# LPDDR4.net
KiCad netlist of a schematic drawn in Altium Designer
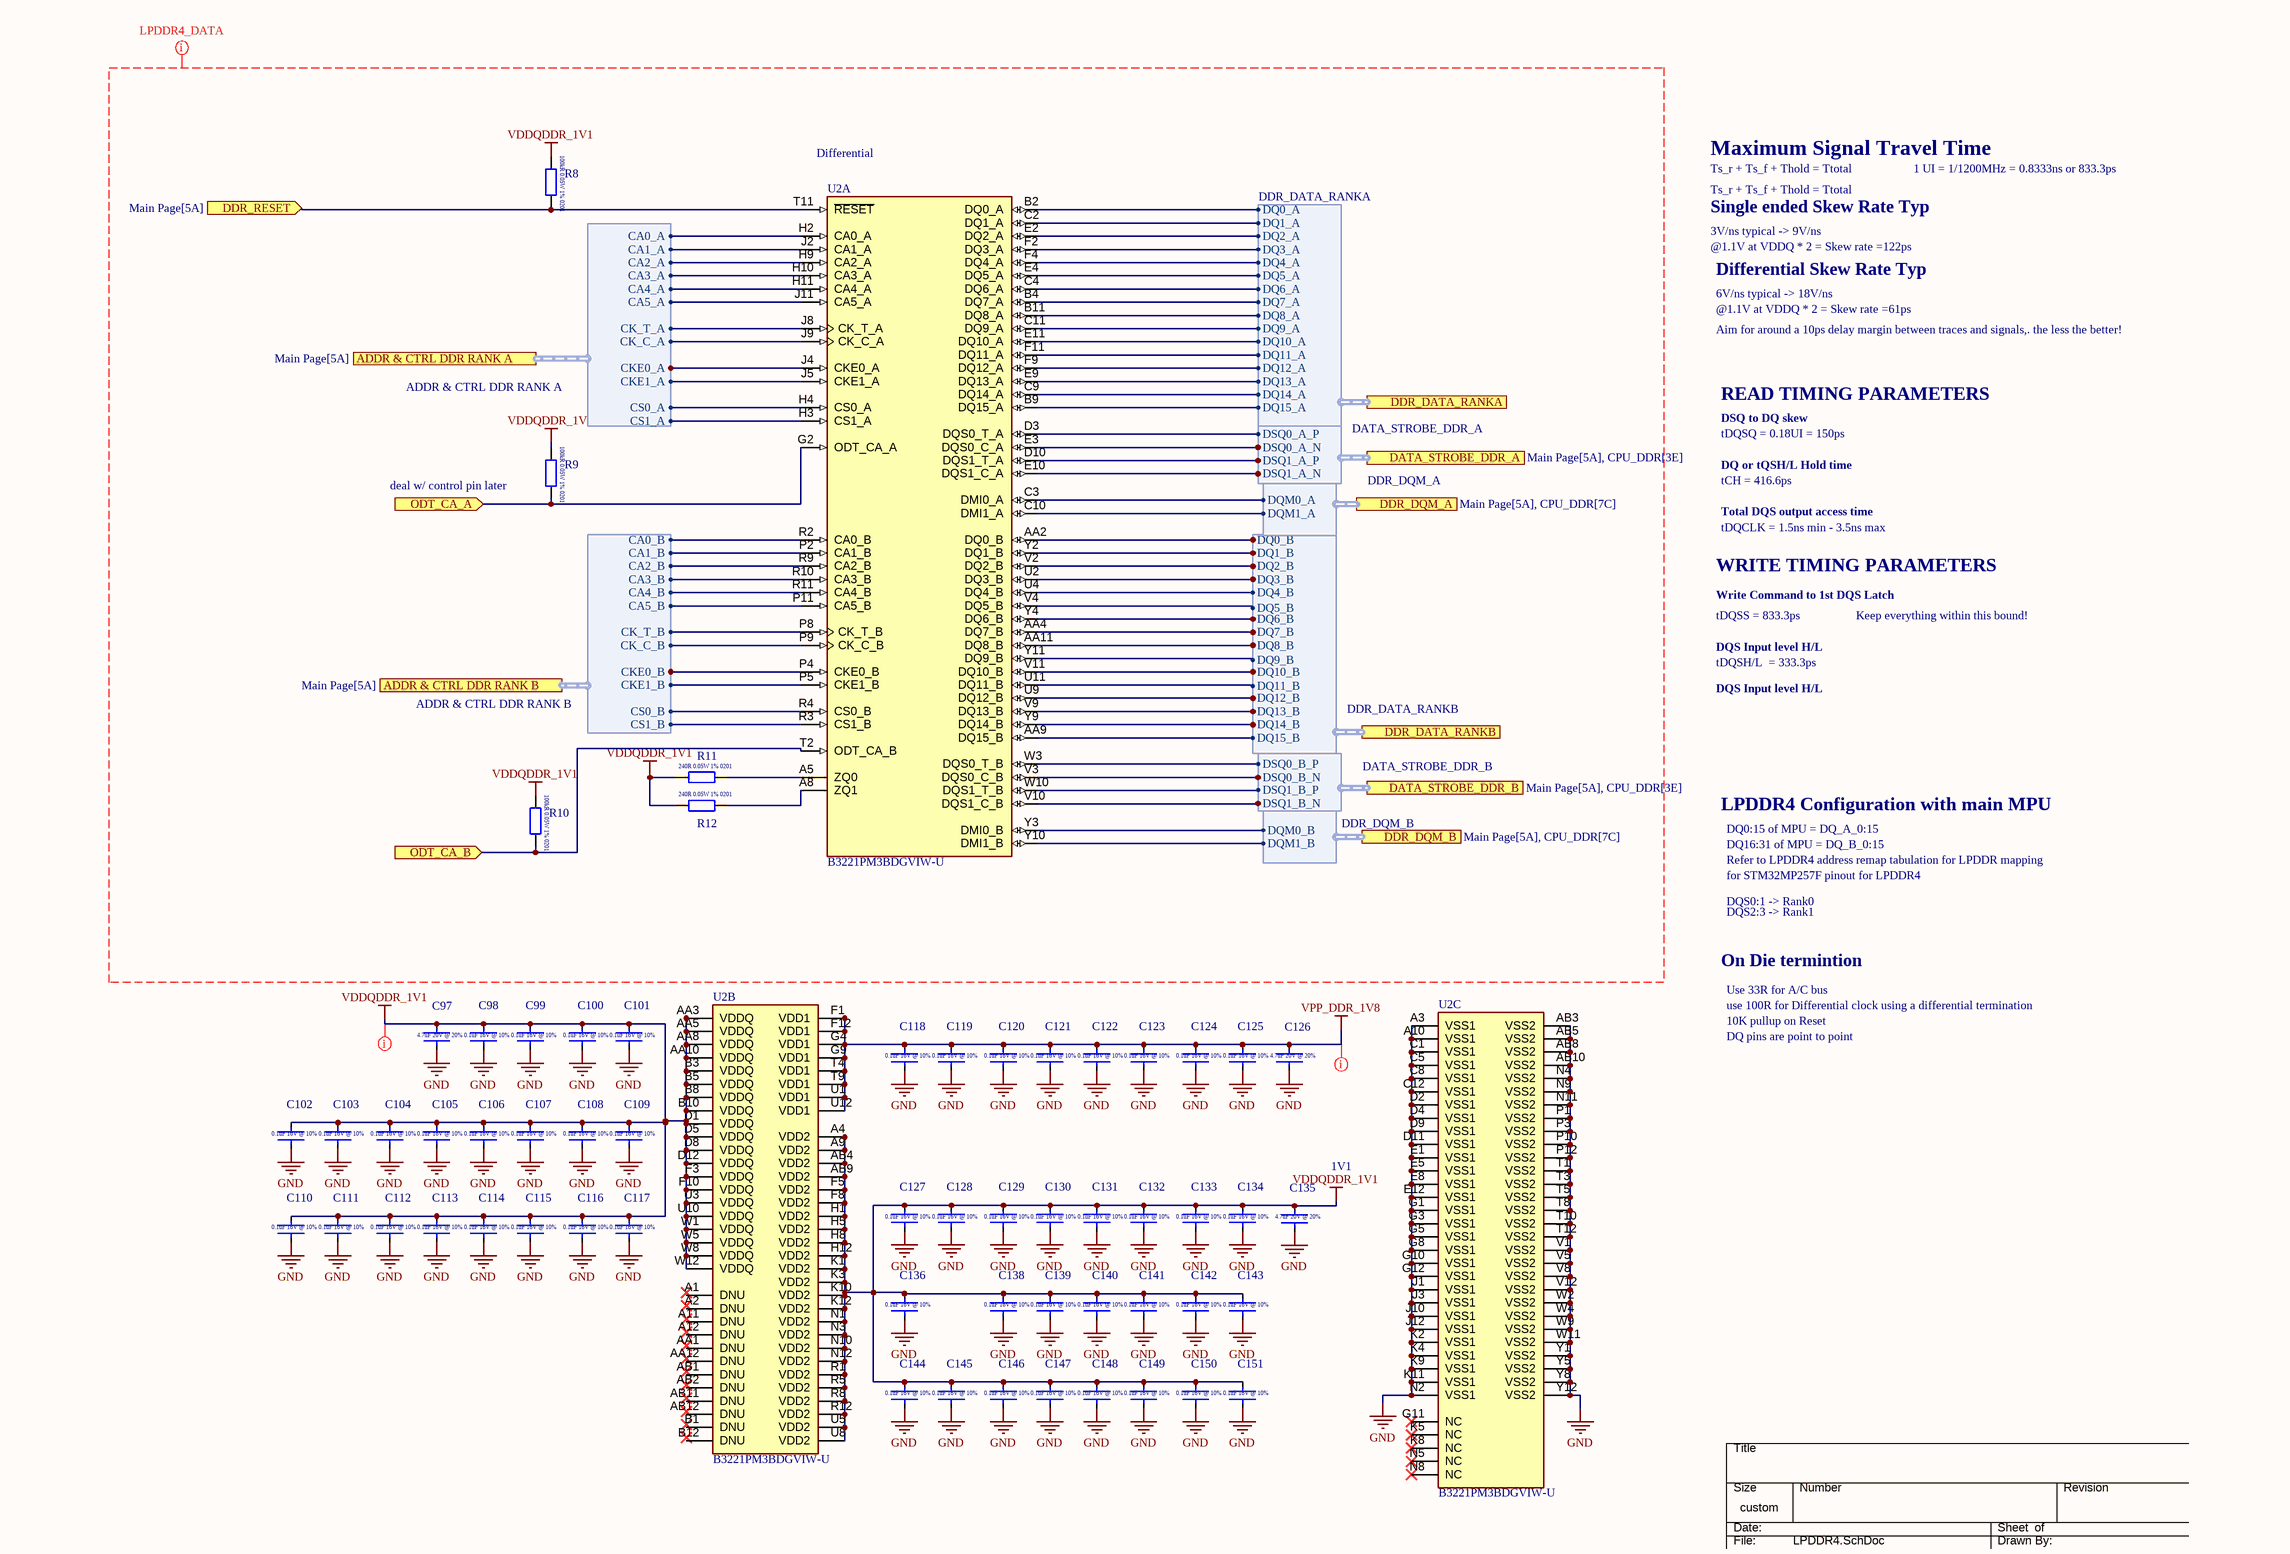
[diagram p0: LPDDR4.SchDoc]

(export (version "E")
  (design (tool "Eeschema 10.0.6"))
  (components
    (comp (ref "C97")
      (value "4.7uF")
      (footprint "CAPC1005X06L")
      (description "4.7 µF ±20% 16V Ceramic Capacitor X5R 0402 (1005 Metric)")
      (libsource (lib "Gesturelink Schematic Library") (part "CL05A475MO5NUNC"))
    )
    (comp (ref "C98")
      (value "0.1uF")
      (footprint "CAPC0603X03L")
      (libsource (lib "Gesturelink Schematic Library") (part "GRM033R61E104KE14J"))
    )
    (comp (ref "C99")
      (value "0.1uF")
      (footprint "CAPC0603X03L")
      (libsource (lib "Gesturelink Schematic Library") (part "GRM033R61E104KE14J"))
    )
    (comp (ref "C100")
      (value "0.1uF")
      (footprint "CAPC0603X03L")
      (libsource (lib "Gesturelink Schematic Library") (part "GRM033R61E104KE14J"))
    )
    (comp (ref "C101")
      (value "0.1uF")
      (footprint "CAPC0603X03L")
      (libsource (lib "Gesturelink Schematic Library") (part "GRM033R61E104KE14J"))
    )
    (comp (ref "C102")
      (value "0.1uF")
      (footprint "CAPC0603X03L")
      (libsource (lib "Gesturelink Schematic Library") (part "GRM033R61E104KE14J"))
    )
    (comp (ref "C103")
      (value "0.1uF")
      (footprint "CAPC0603X03L")
      (libsource (lib "Gesturelink Schematic Library") (part "GRM033R61E104KE14J"))
    )
    (comp (ref "C104")
      (value "0.1uF")
      (footprint "CAPC0603X03L")
      (libsource (lib "Gesturelink Schematic Library") (part "GRM033R61E104KE14J"))
    )
    (comp (ref "C105")
      (value "0.1uF")
      (footprint "CAPC0603X03L")
      (libsource (lib "Gesturelink Schematic Library") (part "GRM033R61E104KE14J"))
    )
    (comp (ref "C106")
      (value "0.1uF")
      (footprint "CAPC0603X03L")
      (libsource (lib "Gesturelink Schematic Library") (part "GRM033R61E104KE14J"))
    )
    (comp (ref "C107")
      (value "0.1uF")
      (footprint "CAPC0603X03L")
      (libsource (lib "Gesturelink Schematic Library") (part "GRM033R61E104KE14J"))
    )
    (comp (ref "C108")
      (value "0.1uF")
      (footprint "CAPC0603X03L")
      (libsource (lib "Gesturelink Schematic Library") (part "GRM033R61E104KE14J"))
    )
    (comp (ref "C109")
      (value "0.1uF")
      (footprint "CAPC0603X03L")
      (libsource (lib "Gesturelink Schematic Library") (part "GRM033R61E104KE14J"))
    )
    (comp (ref "C110")
      (value "0.1uF")
      (footprint "CAPC0603X03L")
      (libsource (lib "Gesturelink Schematic Library") (part "GRM033R61E104KE14J"))
    )
    (comp (ref "C111")
      (value "0.1uF")
      (footprint "CAPC0603X03L")
      (libsource (lib "Gesturelink Schematic Library") (part "GRM033R61E104KE14J"))
    )
    (comp (ref "C112")
      (value "0.1uF")
      (footprint "CAPC0603X03L")
      (libsource (lib "Gesturelink Schematic Library") (part "GRM033R61E104KE14J"))
    )
    (comp (ref "C113")
      (value "0.1uF")
      (footprint "CAPC0603X03L")
      (libsource (lib "Gesturelink Schematic Library") (part "GRM033R61E104KE14J"))
    )
    (comp (ref "C114")
      (value "0.1uF")
      (footprint "CAPC0603X03L")
      (libsource (lib "Gesturelink Schematic Library") (part "GRM033R61E104KE14J"))
    )
    (comp (ref "C115")
      (value "0.1uF")
      (footprint "CAPC0603X03L")
      (libsource (lib "Gesturelink Schematic Library") (part "GRM033R61E104KE14J"))
    )
    (comp (ref "C116")
      (value "0.1uF")
      (footprint "CAPC0603X03L")
      (libsource (lib "Gesturelink Schematic Library") (part "GRM033R61E104KE14J"))
    )
    (comp (ref "C117")
      (value "0.1uF")
      (footprint "CAPC0603X03L")
      (libsource (lib "Gesturelink Schematic Library") (part "GRM033R61E104KE14J"))
    )
    (comp (ref "C118")
      (value "0.1uF")
      (footprint "CAPC0603X03L")
      (libsource (lib "Gesturelink Schematic Library") (part "GRM033R61E104KE14J"))
    )
    (comp (ref "C119")
      (value "0.1uF")
      (footprint "CAPC0603X03L")
      (libsource (lib "Gesturelink Schematic Library") (part "GRM033R61E104KE14J"))
    )
    (comp (ref "C120")
      (value "0.1uF")
      (footprint "CAPC0603X03L")
      (libsource (lib "Gesturelink Schematic Library") (part "GRM033R61E104KE14J"))
    )
    (comp (ref "C121")
      (value "0.1uF")
      (footprint "CAPC0603X03L")
      (libsource (lib "Gesturelink Schematic Library") (part "GRM033R61E104KE14J"))
    )
    (comp (ref "C122")
      (value "0.1uF")
      (footprint "CAPC0603X03L")
      (libsource (lib "Gesturelink Schematic Library") (part "GRM033R61E104KE14J"))
    )
    (comp (ref "C123")
      (value "0.1uF")
      (footprint "CAPC0603X03L")
      (libsource (lib "Gesturelink Schematic Library") (part "GRM033R61E104KE14J"))
    )
    (comp (ref "C124")
      (value "0.1uF")
      (footprint "CAPC0603X03L")
      (libsource (lib "Gesturelink Schematic Library") (part "GRM033R61E104KE14J"))
    )
    (comp (ref "C125")
      (value "0.1uF")
      (footprint "CAPC0603X03L")
      (libsource (lib "Gesturelink Schematic Library") (part "GRM033R61E104KE14J"))
    )
    (comp (ref "C126")
      (value "4.7uF")
      (footprint "CAPC1005X06L")
      (description "4.7 µF ±20% 16V Ceramic Capacitor X5R 0402 (1005 Metric)")
      (libsource (lib "Gesturelink Schematic Library") (part "CL05A475MO5NUNC"))
    )
    (comp (ref "C127")
      (value "0.1uF")
      (footprint "CAPC0603X03L")
      (libsource (lib "Gesturelink Schematic Library") (part "GRM033R61E104KE14J"))
    )
    (comp (ref "C128")
      (value "0.1uF")
      (footprint "CAPC0603X03L")
      (libsource (lib "Gesturelink Schematic Library") (part "GRM033R61E104KE14J"))
    )
    (comp (ref "C129")
      (value "0.1uF")
      (footprint "CAPC0603X03L")
      (libsource (lib "Gesturelink Schematic Library") (part "GRM033R61E104KE14J"))
    )
    (comp (ref "C130")
      (value "0.1uF")
      (footprint "CAPC0603X03L")
      (libsource (lib "Gesturelink Schematic Library") (part "GRM033R61E104KE14J"))
    )
    (comp (ref "C131")
      (value "0.1uF")
      (footprint "CAPC0603X03L")
      (libsource (lib "Gesturelink Schematic Library") (part "GRM033R61E104KE14J"))
    )
    (comp (ref "C132")
      (value "0.1uF")
      (footprint "CAPC0603X03L")
      (libsource (lib "Gesturelink Schematic Library") (part "GRM033R61E104KE14J"))
    )
    (comp (ref "C133")
      (value "0.1uF")
      (footprint "CAPC0603X03L")
      (libsource (lib "Gesturelink Schematic Library") (part "GRM033R61E104KE14J"))
    )
    (comp (ref "C134")
      (value "0.1uF")
      (footprint "CAPC0603X03L")
      (libsource (lib "Gesturelink Schematic Library") (part "GRM033R61E104KE14J"))
    )
    (comp (ref "C135")
      (value "4.7uF")
      (footprint "CAPC1005X06L")
      (description "4.7 µF ±20% 16V Ceramic Capacitor X5R 0402 (1005 Metric)")
      (libsource (lib "Gesturelink Schematic Library") (part "CL05A475MO5NUNC"))
    )
    (comp (ref "C136")
      (value "0.1uF")
      (footprint "CAPC0603X03L")
      (libsource (lib "Gesturelink Schematic Library") (part "GRM033R61E104KE14J"))
    )
    (comp (ref "C138")
      (value "0.1uF")
      (footprint "CAPC0603X03L")
      (libsource (lib "Gesturelink Schematic Library") (part "GRM033R61E104KE14J"))
    )
    (comp (ref "C139")
      (value "0.1uF")
      (footprint "CAPC0603X03L")
      (libsource (lib "Gesturelink Schematic Library") (part "GRM033R61E104KE14J"))
    )
    (comp (ref "C140")
      (value "0.1uF")
      (footprint "CAPC0603X03L")
      (libsource (lib "Gesturelink Schematic Library") (part "GRM033R61E104KE14J"))
    )
    (comp (ref "C141")
      (value "0.1uF")
      (footprint "CAPC0603X03L")
      (libsource (lib "Gesturelink Schematic Library") (part "GRM033R61E104KE14J"))
    )
    (comp (ref "C142")
      (value "0.1uF")
      (footprint "CAPC0603X03L")
      (libsource (lib "Gesturelink Schematic Library") (part "GRM033R61E104KE14J"))
    )
    (comp (ref "C143")
      (value "0.1uF")
      (footprint "CAPC0603X03L")
      (libsource (lib "Gesturelink Schematic Library") (part "GRM033R61E104KE14J"))
    )
    (comp (ref "C144")
      (value "0.1uF")
      (footprint "CAPC0603X03L")
      (libsource (lib "Gesturelink Schematic Library") (part "GRM033R61E104KE14J"))
    )
    (comp (ref "C145")
      (value "0.1uF")
      (footprint "CAPC0603X03L")
      (libsource (lib "Gesturelink Schematic Library") (part "GRM033R61E104KE14J"))
    )
    (comp (ref "C146")
      (value "0.1uF")
      (footprint "CAPC0603X03L")
      (libsource (lib "Gesturelink Schematic Library") (part "GRM033R61E104KE14J"))
    )
    (comp (ref "C147")
      (value "0.1uF")
      (footprint "CAPC0603X03L")
      (libsource (lib "Gesturelink Schematic Library") (part "GRM033R61E104KE14J"))
    )
    (comp (ref "C148")
      (value "0.1uF")
      (footprint "CAPC0603X03L")
      (libsource (lib "Gesturelink Schematic Library") (part "GRM033R61E104KE14J"))
    )
    (comp (ref "C149")
      (value "0.1uF")
      (footprint "CAPC0603X03L")
      (libsource (lib "Gesturelink Schematic Library") (part "GRM033R61E104KE14J"))
    )
    (comp (ref "C150")
      (value "0.1uF")
      (footprint "CAPC0603X03L")
      (libsource (lib "Gesturelink Schematic Library") (part "GRM033R61E104KE14J"))
    )
    (comp (ref "C151")
      (value "0.1uF")
      (footprint "CAPC0603X03L")
      (libsource (lib "Gesturelink Schematic Library") (part "GRM033R61E104KE14J"))
    )
    (comp (ref "R8")
      (value "ERJ-1GNF1003C")
      (footprint "RESC0603X03L")
      (description "100 kOhms ±1% 0.05W, 1/20W Chip Resistor 0201 (0603 Metric) Thick Film")
      (libsource (lib "Resistors") (part "ERJ-1GNF1003C"))
    )
    (comp (ref "R9")
      (value "ERJ-1GNF1003C")
      (footprint "RESC0603X03L")
      (description "100 kOhms ±1% 0.05W, 1/20W Chip Resistor 0201 (0603 Metric) Thick Film")
      (libsource (lib "Resistors") (part "ERJ-1GNF1003C"))
    )
    (comp (ref "R10")
      (value "ERJ-1GNF1003C")
      (footprint "RESC0603X03L")
      (description "100 kOhms ±1% 0.05W, 1/20W Chip Resistor 0201 (0603 Metric) Thick Film")
      (libsource (lib "Resistors") (part "ERJ-1GNF1003C"))
    )
    (comp (ref "R11")
      (value "ERJ-1GNF2400C")
      (footprint "RESC0603X03L")
      (libsource (lib "Resistors") (part "ERJ-1GNF2400C"))
    )
    (comp (ref "R12")
      (value "ERJ-1GNF2400C")
      (footprint "RESC0603X03L")
      (libsource (lib "Resistors") (part "ERJ-1GNF2400C"))
    )
    (comp (ref "U2")
      (value "B3221PM3BDGVIW-U")
      (footprint "Q6422PM3BDGVK-U")
      (description "SDRAM - Mobile LPDDR4 Memory IC 64Gbit 2.133 GHz 3.5 ns 200-FBGA (10x14.5)")
      (fields (field (name "MP") "Q6422PM3BDGVK-U"))
      (libsource (lib "Gesturelink Schematic Library") (part "Q6422PM3BDGVK-U"))
    )
  )
  (nets
    (net (code "14") (name "/CA0_A") (class "Default")
      (node (ref "U2") (pin "H2") (pinfunction "CA0_A_H2") (pintype "input"))
    )
    (net (code "15") (name "/CA0_B") (class "Default")
      (node (ref "U2") (pin "R2") (pinfunction "CA0_B_R2") (pintype "input"))
    )
    (net (code "16") (name "/CA1_A") (class "Default")
      (node (ref "U2") (pin "J2") (pinfunction "CA1_A_J2") (pintype "input"))
    )
    (net (code "17") (name "/CA1_B") (class "Default")
      (node (ref "U2") (pin "P2") (pinfunction "CA1_B_P2") (pintype "input"))
    )
    (net (code "18") (name "/CA2_A") (class "Default")
      (node (ref "U2") (pin "H9") (pinfunction "CA2_A_H9") (pintype "input"))
    )
    (net (code "19") (name "/CA2_B") (class "Default")
      (node (ref "U2") (pin "R9") (pinfunction "CA2_B_R9") (pintype "input"))
    )
    (net (code "20") (name "/CA3_A") (class "Default")
      (node (ref "U2") (pin "H10") (pinfunction "CA3_A_H10") (pintype "input"))
    )
    (net (code "21") (name "/CA3_B") (class "Default")
      (node (ref "U2") (pin "R10") (pinfunction "CA3_B_R10") (pintype "input"))
    )
    (net (code "22") (name "/CA4_A") (class "Default")
      (node (ref "U2") (pin "H11") (pinfunction "CA4_A_H11") (pintype "input"))
    )
    (net (code "23") (name "/CA4_B") (class "Default")
      (node (ref "U2") (pin "R11") (pinfunction "CA4_B_R11") (pintype "input"))
    )
    (net (code "24") (name "/CA5_A") (class "Default")
      (node (ref "U2") (pin "J11") (pinfunction "CA5_A_J11") (pintype "input"))
    )
    (net (code "25") (name "/CA5_B") (class "Default")
      (node (ref "U2") (pin "P11") (pinfunction "CA5_B_P11") (pintype "input"))
    )
    (net (code "26") (name "/CKE0_A") (class "Default")
      (node (ref "U2") (pin "J4") (pinfunction "CKE0_A_J4") (pintype "input"))
    )
    (net (code "27") (name "/CKE0_B") (class "Default")
      (node (ref "U2") (pin "P4") (pinfunction "CKE0_B_P4") (pintype "input"))
    )
    (net (code "28") (name "/CKE1_A") (class "Default")
      (node (ref "U2") (pin "J5") (pinfunction "CKE1_A_J5") (pintype "input"))
    )
    (net (code "29") (name "/CKE1_B") (class "Default")
      (node (ref "U2") (pin "P5") (pinfunction "CKE1_B_P5") (pintype "input"))
    )
    (net (code "30") (name "/CK_C_A") (class "Default")
      (node (ref "U2") (pin "J9") (pinfunction "CK_C_A_J9") (pintype "input"))
    )
    (net (code "31") (name "/CK_C_B") (class "Default")
      (node (ref "U2") (pin "P9") (pinfunction "CK_C_B_P9") (pintype "input"))
    )
    (net (code "32") (name "/CK_T_A") (class "Default")
      (node (ref "U2") (pin "J8") (pinfunction "CK_T_A_J8") (pintype "input"))
    )
    (net (code "33") (name "/CK_T_B") (class "Default")
      (node (ref "U2") (pin "P8") (pinfunction "CK_T_B_P8") (pintype "input"))
    )
    (net (code "34") (name "/CS0_A") (class "Default")
      (node (ref "U2") (pin "H4") (pinfunction "CS0_A_H4") (pintype "input"))
    )
    (net (code "35") (name "/CS0_B") (class "Default")
      (node (ref "U2") (pin "R4") (pinfunction "CS0_B_R4") (pintype "input"))
    )
    (net (code "36") (name "/CS1_A") (class "Default")
      (node (ref "U2") (pin "H3") (pinfunction "CS1_A_H3") (pintype "input"))
    )
    (net (code "37") (name "/CS1_B") (class "Default")
      (node (ref "U2") (pin "R3") (pinfunction "CS1_B_R3") (pintype "input"))
    )
    (net (code "38") (name "/DDR_RESET") (class "Default")
      (node (ref "R8") (pin "2") (pinfunction "2_2") (pintype "passive"))
      (node (ref "U2") (pin "T11") (pinfunction "~{RESET}_T11") (pintype "input"))
    )
    (net (code "39") (name "/DQ0_A") (class "Default")
      (node (ref "U2") (pin "B2") (pinfunction "DQ0_A_B2") (pintype "bidirectional"))
    )
    (net (code "40") (name "/DQ0_B") (class "Default")
      (node (ref "U2") (pin "AA2") (pinfunction "DQ0_B_AA2") (pintype "bidirectional"))
    )
    (net (code "41") (name "/DQ1_A") (class "Default")
      (node (ref "U2") (pin "C2") (pinfunction "DQ1_A_C2") (pintype "bidirectional"))
    )
    (net (code "42") (name "/DQ1_B") (class "Default")
      (node (ref "U2") (pin "Y2") (pinfunction "DQ1_B_Y2") (pintype "bidirectional"))
    )
    (net (code "43") (name "/DQ2_A") (class "Default")
      (node (ref "U2") (pin "E2") (pinfunction "DQ2_A_E2") (pintype "bidirectional"))
    )
    (net (code "44") (name "/DQ2_B") (class "Default")
      (node (ref "U2") (pin "V2") (pinfunction "DQ2_B_V2") (pintype "bidirectional"))
    )
    (net (code "45") (name "/DQ3_A") (class "Default")
      (node (ref "U2") (pin "F2") (pinfunction "DQ3_A_F2") (pintype "bidirectional"))
    )
    (net (code "46") (name "/DQ3_B") (class "Default")
      (node (ref "U2") (pin "U2") (pinfunction "DQ3_B_U2") (pintype "bidirectional"))
    )
    (net (code "47") (name "/DQ4_A") (class "Default")
      (node (ref "U2") (pin "F4") (pinfunction "DQ4_A_F4") (pintype "bidirectional"))
    )
    (net (code "48") (name "/DQ4_B") (class "Default")
      (node (ref "U2") (pin "U4") (pinfunction "DQ4_B_U4") (pintype "bidirectional"))
    )
    (net (code "49") (name "/DQ5_A") (class "Default")
      (node (ref "U2") (pin "E4") (pinfunction "DQ5_A_E4") (pintype "bidirectional"))
    )
    (net (code "50") (name "/DQ5_B") (class "Default")
      (node (ref "U2") (pin "V4") (pinfunction "DQ5_B_V4") (pintype "bidirectional"))
    )
    (net (code "51") (name "/DQ6_A") (class "Default")
      (node (ref "U2") (pin "C4") (pinfunction "DQ6_A_C4") (pintype "bidirectional"))
    )
    (net (code "52") (name "/DQ6_B") (class "Default")
      (node (ref "U2") (pin "Y4") (pinfunction "DQ6_B_Y4") (pintype "bidirectional"))
    )
    (net (code "53") (name "/DQ7_A") (class "Default")
      (node (ref "U2") (pin "B4") (pinfunction "DQ7_A_B4") (pintype "bidirectional"))
    )
    (net (code "54") (name "/DQ7_B") (class "Default")
      (node (ref "U2") (pin "AA4") (pinfunction "DQ7_B_AA4") (pintype "bidirectional"))
    )
    (net (code "55") (name "/DQ8_A") (class "Default")
      (node (ref "U2") (pin "B11") (pinfunction "DQ8_A_B11") (pintype "bidirectional"))
    )
    (net (code "56") (name "/DQ8_B") (class "Default")
      (node (ref "U2") (pin "AA11") (pinfunction "DQ8_B_AA11") (pintype "bidirectional"))
    )
    (net (code "57") (name "/DQ9_A") (class "Default")
      (node (ref "U2") (pin "C11") (pinfunction "DQ9_A_C11") (pintype "bidirectional"))
    )
    (net (code "58") (name "/DQ9_B") (class "Default")
      (node (ref "U2") (pin "Y11") (pinfunction "DQ9_B_Y11") (pintype "bidirectional"))
    )
    (net (code "59") (name "/DQ10_A") (class "Default")
      (node (ref "U2") (pin "E11") (pinfunction "DQ10_A_E11") (pintype "bidirectional"))
    )
    (net (code "60") (name "/DQ10_B") (class "Default")
      (node (ref "U2") (pin "V11") (pinfunction "DQ10_B_V11") (pintype "bidirectional"))
    )
    (net (code "61") (name "/DQ11_A") (class "Default")
      (node (ref "U2") (pin "F11") (pinfunction "DQ11_A_F11") (pintype "bidirectional"))
    )
    (net (code "62") (name "/DQ11_B") (class "Default")
      (node (ref "U2") (pin "U11") (pinfunction "DQ11_B_U11") (pintype "bidirectional"))
    )
    (net (code "63") (name "/DQ12_A") (class "Default")
      (node (ref "U2") (pin "F9") (pinfunction "DQ12_A_F9") (pintype "bidirectional"))
    )
    (net (code "64") (name "/DQ12_B") (class "Default")
      (node (ref "U2") (pin "U9") (pinfunction "DQ12_B_U9") (pintype "bidirectional"))
    )
    (net (code "65") (name "/DQ13_A") (class "Default")
      (node (ref "U2") (pin "E9") (pinfunction "DQ13_A_E9") (pintype "bidirectional"))
    )
    (net (code "66") (name "/DQ13_B") (class "Default")
      (node (ref "U2") (pin "V9") (pinfunction "DQ13_B_V9") (pintype "bidirectional"))
    )
    (net (code "67") (name "/DQ14_A") (class "Default")
      (node (ref "U2") (pin "C9") (pinfunction "DQ14_A_C9") (pintype "bidirectional"))
    )
    (net (code "68") (name "/DQ14_B") (class "Default")
      (node (ref "U2") (pin "Y9") (pinfunction "DQ14_B_Y9") (pintype "bidirectional"))
    )
    (net (code "69") (name "/DQ15_A") (class "Default")
      (node (ref "U2") (pin "B9") (pinfunction "DQ15_A_B9") (pintype "bidirectional"))
    )
    (net (code "70") (name "/DQ15_B") (class "Default")
      (node (ref "U2") (pin "AA9") (pinfunction "DQ15_B_AA9") (pintype "bidirectional"))
    )
    (net (code "71") (name "/DQM0_A") (class "Default")
      (node (ref "U2") (pin "C3") (pinfunction "DMI0_A_C3") (pintype "bidirectional"))
    )
    (net (code "72") (name "/DQM0_B") (class "Default")
      (node (ref "U2") (pin "Y3") (pinfunction "DMI0_B_Y3") (pintype "bidirectional"))
    )
    (net (code "73") (name "/DQM1_A") (class "Default")
      (node (ref "U2") (pin "C10") (pinfunction "DMI1_A_C10") (pintype "bidirectional"))
    )
    (net (code "74") (name "/DQM1_B") (class "Default")
      (node (ref "U2") (pin "Y10") (pinfunction "DMI1_B_Y10") (pintype "bidirectional"))
    )
    (net (code "75") (name "/DSQ0_A_N") (class "Default")
      (node (ref "U2") (pin "E3") (pinfunction "DQS0_C_A_E3") (pintype "bidirectional"))
    )
    (net (code "76") (name "/DSQ0_A_P") (class "Default")
      (node (ref "U2") (pin "D3") (pinfunction "DQS0_T_A_D3") (pintype "bidirectional"))
    )
    (net (code "77") (name "/DSQ0_B_N") (class "Default")
      (node (ref "U2") (pin "V3") (pinfunction "DQS0_C_B_V3") (pintype "bidirectional"))
    )
    (net (code "78") (name "/DSQ0_B_P") (class "Default")
      (node (ref "U2") (pin "W3") (pinfunction "DQS0_T_B_W3") (pintype "bidirectional"))
    )
    (net (code "79") (name "/DSQ1_A_N") (class "Default")
      (node (ref "U2") (pin "E10") (pinfunction "DQS1_C_A_E10") (pintype "bidirectional"))
    )
    (net (code "80") (name "/DSQ1_A_P") (class "Default")
      (node (ref "U2") (pin "D10") (pinfunction "DQS1_T_A_D10") (pintype "bidirectional"))
    )
    (net (code "81") (name "/DSQ1_B_N") (class "Default")
      (node (ref "U2") (pin "V10") (pinfunction "DQS1_C_B_V10") (pintype "bidirectional"))
    )
    (net (code "82") (name "/DSQ1_B_P") (class "Default")
      (node (ref "U2") (pin "W10") (pinfunction "DQS1_T_B_W10") (pintype "bidirectional"))
    )
    (net (code "83") (name "/ODT_CA_A") (class "Default")
      (node (ref "R9") (pin "2") (pinfunction "2_2") (pintype "passive"))
      (node (ref "U2") (pin "G2") (pinfunction "ODT_CA_A_G2") (pintype "input"))
    )
    (net (code "84") (name "/ODT_CA_B") (class "Default")
      (node (ref "R10") (pin "2") (pinfunction "2_2") (pintype "passive"))
      (node (ref "U2") (pin "T2") (pinfunction "ODT_CA_B_T2") (pintype "input"))
    )
    (net (code "93") (name "GND") (class "Default")
      (node (ref "C100") (pin "1") (pinfunction "1_1") (pintype "passive"))
      (node (ref "C101") (pin "1") (pinfunction "1_1") (pintype "passive"))
      (node (ref "C102") (pin "1") (pinfunction "1_1") (pintype "passive"))
      (node (ref "C103") (pin "1") (pinfunction "1_1") (pintype "passive"))
      (node (ref "C104") (pin "1") (pinfunction "1_1") (pintype "passive"))
      (node (ref "C105") (pin "1") (pinfunction "1_1") (pintype "passive"))
      (node (ref "C106") (pin "1") (pinfunction "1_1") (pintype "passive"))
      (node (ref "C107") (pin "1") (pinfunction "1_1") (pintype "passive"))
      (node (ref "C108") (pin "1") (pinfunction "1_1") (pintype "passive"))
      (node (ref "C109") (pin "1") (pinfunction "1_1") (pintype "passive"))
      (node (ref "C110") (pin "1") (pinfunction "1_1") (pintype "passive"))
      (node (ref "C111") (pin "1") (pinfunction "1_1") (pintype "passive"))
      (node (ref "C112") (pin "1") (pinfunction "1_1") (pintype "passive"))
      (node (ref "C113") (pin "1") (pinfunction "1_1") (pintype "passive"))
      (node (ref "C114") (pin "1") (pinfunction "1_1") (pintype "passive"))
      (node (ref "C115") (pin "1") (pinfunction "1_1") (pintype "passive"))
      (node (ref "C116") (pin "1") (pinfunction "1_1") (pintype "passive"))
      (node (ref "C117") (pin "1") (pinfunction "1_1") (pintype "passive"))
      (node (ref "C118") (pin "1") (pinfunction "1_1") (pintype "passive"))
      (node (ref "C119") (pin "1") (pinfunction "1_1") (pintype "passive"))
      (node (ref "C120") (pin "1") (pinfunction "1_1") (pintype "passive"))
      (node (ref "C121") (pin "1") (pinfunction "1_1") (pintype "passive"))
      (node (ref "C122") (pin "1") (pinfunction "1_1") (pintype "passive"))
      (node (ref "C123") (pin "1") (pinfunction "1_1") (pintype "passive"))
      (node (ref "C124") (pin "1") (pinfunction "1_1") (pintype "passive"))
      (node (ref "C125") (pin "1") (pinfunction "1_1") (pintype "passive"))
      (node (ref "C126") (pin "1") (pinfunction "1_1") (pintype "passive"))
      (node (ref "C127") (pin "1") (pinfunction "1_1") (pintype "passive"))
      (node (ref "C128") (pin "1") (pinfunction "1_1") (pintype "passive"))
      (node (ref "C129") (pin "1") (pinfunction "1_1") (pintype "passive"))
      (node (ref "C130") (pin "1") (pinfunction "1_1") (pintype "passive"))
      (node (ref "C131") (pin "1") (pinfunction "1_1") (pintype "passive"))
      (node (ref "C132") (pin "1") (pinfunction "1_1") (pintype "passive"))
      (node (ref "C133") (pin "1") (pinfunction "1_1") (pintype "passive"))
      (node (ref "C134") (pin "1") (pinfunction "1_1") (pintype "passive"))
      (node (ref "C135") (pin "1") (pinfunction "1_1") (pintype "passive"))
      (node (ref "C136") (pin "1") (pinfunction "1_1") (pintype "passive"))
      (node (ref "C138") (pin "1") (pinfunction "1_1") (pintype "passive"))
      (node (ref "C139") (pin "1") (pinfunction "1_1") (pintype "passive"))
      (node (ref "C140") (pin "1") (pinfunction "1_1") (pintype "passive"))
      (node (ref "C141") (pin "1") (pinfunction "1_1") (pintype "passive"))
      (node (ref "C142") (pin "1") (pinfunction "1_1") (pintype "passive"))
      (node (ref "C143") (pin "1") (pinfunction "1_1") (pintype "passive"))
      (node (ref "C144") (pin "1") (pinfunction "1_1") (pintype "passive"))
      (node (ref "C145") (pin "1") (pinfunction "1_1") (pintype "passive"))
      (node (ref "C146") (pin "1") (pinfunction "1_1") (pintype "passive"))
      (node (ref "C147") (pin "1") (pinfunction "1_1") (pintype "passive"))
      (node (ref "C148") (pin "1") (pinfunction "1_1") (pintype "passive"))
      (node (ref "C149") (pin "1") (pinfunction "1_1") (pintype "passive"))
      (node (ref "C150") (pin "1") (pinfunction "1_1") (pintype "passive"))
      (node (ref "C151") (pin "1") (pinfunction "1_1") (pintype "passive"))
      (node (ref "C97") (pin "1") (pinfunction "1_1") (pintype "passive"))
      (node (ref "C98") (pin "1") (pinfunction "1_1") (pintype "passive"))
      (node (ref "C99") (pin "1") (pinfunction "1_1") (pintype "passive"))
      (node (ref "U2") (pin "A10") (pinfunction "VSS1_A10") (pintype "power_in"))
      (node (ref "U2") (pin "A3") (pinfunction "VSS1_A3") (pintype "power_in"))
      (node (ref "U2") (pin "AB10") (pinfunction "VSS2_AB10") (pintype "power_in"))
      (node (ref "U2") (pin "AB3") (pinfunction "VSS2_AB3") (pintype "power_in"))
      (node (ref "U2") (pin "AB5") (pinfunction "VSS2_AB5") (pintype "power_in"))
      (node (ref "U2") (pin "AB8") (pinfunction "VSS2_AB8") (pintype "power_in"))
      (node (ref "U2") (pin "C1") (pinfunction "VSS1_C1") (pintype "power_in"))
      (node (ref "U2") (pin "C12") (pinfunction "VSS1_C12") (pintype "power_in"))
      (node (ref "U2") (pin "C5") (pinfunction "VSS1_C5") (pintype "power_in"))
      (node (ref "U2") (pin "C8") (pinfunction "VSS1_C8") (pintype "power_in"))
      (node (ref "U2") (pin "D11") (pinfunction "VSS1_D11") (pintype "power_in"))
      (node (ref "U2") (pin "D2") (pinfunction "VSS1_D2") (pintype "power_in"))
      (node (ref "U2") (pin "D4") (pinfunction "VSS1_D4") (pintype "power_in"))
      (node (ref "U2") (pin "D9") (pinfunction "VSS1_D9") (pintype "power_in"))
      (node (ref "U2") (pin "E1") (pinfunction "VSS1_E1") (pintype "power_in"))
      (node (ref "U2") (pin "E12") (pinfunction "VSS1_E12") (pintype "power_in"))
      (node (ref "U2") (pin "E5") (pinfunction "VSS1_E5") (pintype "power_in"))
      (node (ref "U2") (pin "E8") (pinfunction "VSS1_E8") (pintype "power_in"))
      (node (ref "U2") (pin "G1") (pinfunction "VSS1_G1") (pintype "power_in"))
      (node (ref "U2") (pin "G10") (pinfunction "VSS1_G10") (pintype "power_in"))
      (node (ref "U2") (pin "G12") (pinfunction "VSS1_G12") (pintype "power_in"))
      (node (ref "U2") (pin "G3") (pinfunction "VSS1_G3") (pintype "power_in"))
      (node (ref "U2") (pin "G5") (pinfunction "VSS1_G5") (pintype "power_in"))
      (node (ref "U2") (pin "G8") (pinfunction "VSS1_G8") (pintype "power_in"))
      (node (ref "U2") (pin "J1") (pinfunction "VSS1_J1") (pintype "power_in"))
      (node (ref "U2") (pin "J10") (pinfunction "VSS1_J10") (pintype "power_in"))
      (node (ref "U2") (pin "J12") (pinfunction "VSS1_J12") (pintype "power_in"))
      (node (ref "U2") (pin "J3") (pinfunction "VSS1_J3") (pintype "power_in"))
      (node (ref "U2") (pin "K11") (pinfunction "VSS1_K11") (pintype "power_in"))
      (node (ref "U2") (pin "K2") (pinfunction "VSS1_K2") (pintype "power_in"))
      (node (ref "U2") (pin "K4") (pinfunction "VSS1_K4") (pintype "power_in"))
      (node (ref "U2") (pin "K9") (pinfunction "VSS1_K9") (pintype "power_in"))
      (node (ref "U2") (pin "N11") (pinfunction "VSS2_N11") (pintype "power_in"))
      (node (ref "U2") (pin "N2") (pinfunction "VSS1_N2") (pintype "power_in"))
      (node (ref "U2") (pin "N4") (pinfunction "VSS2_N4") (pintype "power_in"))
      (node (ref "U2") (pin "N9") (pinfunction "VSS2_N9") (pintype "power_in"))
      (node (ref "U2") (pin "P1") (pinfunction "VSS2_P1") (pintype "power_in"))
      (node (ref "U2") (pin "P10") (pinfunction "VSS2_P10") (pintype "power_in"))
      (node (ref "U2") (pin "P12") (pinfunction "VSS2_P12") (pintype "power_in"))
      (node (ref "U2") (pin "P3") (pinfunction "VSS2_P3") (pintype "power_in"))
      (node (ref "U2") (pin "T1") (pinfunction "VSS2_T1") (pintype "power_in"))
      (node (ref "U2") (pin "T10") (pinfunction "VSS2_T10") (pintype "power_in"))
      (node (ref "U2") (pin "T12") (pinfunction "VSS2_T12") (pintype "power_in"))
      (node (ref "U2") (pin "T3") (pinfunction "VSS2_T3") (pintype "power_in"))
      (node (ref "U2") (pin "T5") (pinfunction "VSS2_T5") (pintype "power_in"))
      (node (ref "U2") (pin "T8") (pinfunction "VSS2_T8") (pintype "power_in"))
      (node (ref "U2") (pin "V1") (pinfunction "VSS2_V1") (pintype "power_in"))
      (node (ref "U2") (pin "V12") (pinfunction "VSS2_V12") (pintype "power_in"))
      (node (ref "U2") (pin "V5") (pinfunction "VSS2_V5") (pintype "power_in"))
      (node (ref "U2") (pin "V8") (pinfunction "VSS2_V8") (pintype "power_in"))
      (node (ref "U2") (pin "W11") (pinfunction "VSS2_W11") (pintype "power_in"))
      (node (ref "U2") (pin "W2") (pinfunction "VSS2_W2") (pintype "power_in"))
      (node (ref "U2") (pin "W4") (pinfunction "VSS2_W4") (pintype "power_in"))
      (node (ref "U2") (pin "W9") (pinfunction "VSS2_W9") (pintype "power_in"))
      (node (ref "U2") (pin "Y1") (pinfunction "VSS2_Y1") (pintype "power_in"))
      (node (ref "U2") (pin "Y12") (pinfunction "VSS2_Y12") (pintype "power_in"))
      (node (ref "U2") (pin "Y5") (pinfunction "VSS2_Y5") (pintype "power_in"))
      (node (ref "U2") (pin "Y8") (pinfunction "VSS2_Y8") (pintype "power_in"))
    )
    (net (code "94") (name "Net-(U2A-ZQ0)") (class "Default")
      (node (ref "R11") (pin "2") (pinfunction "2_2") (pintype "passive"))
      (node (ref "U2") (pin "A5") (pinfunction "ZQ0_A5") (pintype "passive"))
    )
    (net (code "95") (name "Net-(U2A-ZQ1)") (class "Default")
      (node (ref "R12") (pin "2") (pinfunction "2_2") (pintype "passive"))
      (node (ref "U2") (pin "A8") (pinfunction "ZQ1_A8") (pintype "passive"))
    )
    (net (code "96") (name "VDDQDDR_1V1") (class "Default")
      (node (ref "C100") (pin "2") (pinfunction "2_2") (pintype "passive"))
      (node (ref "C101") (pin "2") (pinfunction "2_2") (pintype "passive"))
      (node (ref "C102") (pin "2") (pinfunction "2_2") (pintype "passive"))
      (node (ref "C103") (pin "2") (pinfunction "2_2") (pintype "passive"))
      (node (ref "C104") (pin "2") (pinfunction "2_2") (pintype "passive"))
      (node (ref "C105") (pin "2") (pinfunction "2_2") (pintype "passive"))
      (node (ref "C106") (pin "2") (pinfunction "2_2") (pintype "passive"))
      (node (ref "C107") (pin "2") (pinfunction "2_2") (pintype "passive"))
      (node (ref "C108") (pin "2") (pinfunction "2_2") (pintype "passive"))
      (node (ref "C109") (pin "2") (pinfunction "2_2") (pintype "passive"))
      (node (ref "C110") (pin "2") (pinfunction "2_2") (pintype "passive"))
      (node (ref "C111") (pin "2") (pinfunction "2_2") (pintype "passive"))
      (node (ref "C112") (pin "2") (pinfunction "2_2") (pintype "passive"))
      (node (ref "C113") (pin "2") (pinfunction "2_2") (pintype "passive"))
      (node (ref "C114") (pin "2") (pinfunction "2_2") (pintype "passive"))
      (node (ref "C115") (pin "2") (pinfunction "2_2") (pintype "passive"))
      (node (ref "C116") (pin "2") (pinfunction "2_2") (pintype "passive"))
      (node (ref "C117") (pin "2") (pinfunction "2_2") (pintype "passive"))
      (node (ref "C127") (pin "2") (pinfunction "2_2") (pintype "passive"))
      (node (ref "C128") (pin "2") (pinfunction "2_2") (pintype "passive"))
      (node (ref "C129") (pin "2") (pinfunction "2_2") (pintype "passive"))
      (node (ref "C130") (pin "2") (pinfunction "2_2") (pintype "passive"))
      (node (ref "C131") (pin "2") (pinfunction "2_2") (pintype "passive"))
      (node (ref "C132") (pin "2") (pinfunction "2_2") (pintype "passive"))
      (node (ref "C133") (pin "2") (pinfunction "2_2") (pintype "passive"))
      (node (ref "C134") (pin "2") (pinfunction "2_2") (pintype "passive"))
      (node (ref "C135") (pin "2") (pinfunction "2_2") (pintype "passive"))
      (node (ref "C136") (pin "2") (pinfunction "2_2") (pintype "passive"))
      (node (ref "C138") (pin "2") (pinfunction "2_2") (pintype "passive"))
      (node (ref "C139") (pin "2") (pinfunction "2_2") (pintype "passive"))
      (node (ref "C140") (pin "2") (pinfunction "2_2") (pintype "passive"))
      (node (ref "C141") (pin "2") (pinfunction "2_2") (pintype "passive"))
      (node (ref "C142") (pin "2") (pinfunction "2_2") (pintype "passive"))
      (node (ref "C143") (pin "2") (pinfunction "2_2") (pintype "passive"))
      (node (ref "C144") (pin "2") (pinfunction "2_2") (pintype "passive"))
      (node (ref "C145") (pin "2") (pinfunction "2_2") (pintype "passive"))
      (node (ref "C146") (pin "2") (pinfunction "2_2") (pintype "passive"))
      (node (ref "C147") (pin "2") (pinfunction "2_2") (pintype "passive"))
      (node (ref "C148") (pin "2") (pinfunction "2_2") (pintype "passive"))
      (node (ref "C149") (pin "2") (pinfunction "2_2") (pintype "passive"))
      (node (ref "C150") (pin "2") (pinfunction "2_2") (pintype "passive"))
      (node (ref "C151") (pin "2") (pinfunction "2_2") (pintype "passive"))
      (node (ref "C97") (pin "2") (pinfunction "2_2") (pintype "passive"))
      (node (ref "C98") (pin "2") (pinfunction "2_2") (pintype "passive"))
      (node (ref "C99") (pin "2") (pinfunction "2_2") (pintype "passive"))
      (node (ref "R10") (pin "1") (pinfunction "1_1") (pintype "passive"))
      (node (ref "R11") (pin "1") (pinfunction "1_1") (pintype "passive"))
      (node (ref "R12") (pin "1") (pinfunction "1_1") (pintype "passive"))
      (node (ref "R8") (pin "1") (pinfunction "1_1") (pintype "passive"))
      (node (ref "R9") (pin "1") (pinfunction "1_1") (pintype "passive"))
      (node (ref "U2") (pin "A4") (pinfunction "VDD2_A4") (pintype "power_in"))
      (node (ref "U2") (pin "A9") (pinfunction "VDD2_A9") (pintype "power_in"))
      (node (ref "U2") (pin "AA10") (pinfunction "VDDQ_AA10") (pintype "power_in"))
      (node (ref "U2") (pin "AA3") (pinfunction "VDDQ_AA3") (pintype "power_in"))
      (node (ref "U2") (pin "AA5") (pinfunction "VDDQ_AA5") (pintype "power_in"))
      (node (ref "U2") (pin "AA8") (pinfunction "VDDQ_AA8") (pintype "power_in"))
      (node (ref "U2") (pin "AB4") (pinfunction "VDD2_AB4") (pintype "power_in"))
      (node (ref "U2") (pin "AB9") (pinfunction "VDD2_AB9") (pintype "power_in"))
      (node (ref "U2") (pin "B10") (pinfunction "VDDQ_B10") (pintype "power_in"))
      (node (ref "U2") (pin "B3") (pinfunction "VDDQ_B3") (pintype "power_in"))
      (node (ref "U2") (pin "B5") (pinfunction "VDDQ_B5") (pintype "power_in"))
      (node (ref "U2") (pin "B8") (pinfunction "VDDQ_B8") (pintype "power_in"))
      (node (ref "U2") (pin "D1") (pinfunction "VDDQ_D1") (pintype "power_in"))
      (node (ref "U2") (pin "D12") (pinfunction "VDDQ_D12") (pintype "power_in"))
      (node (ref "U2") (pin "D5") (pinfunction "VDDQ_D5") (pintype "power_in"))
      (node (ref "U2") (pin "D8") (pinfunction "VDDQ_D8") (pintype "power_in"))
      (node (ref "U2") (pin "F10") (pinfunction "VDDQ_F10") (pintype "power_in"))
      (node (ref "U2") (pin "F3") (pinfunction "VDDQ_F3") (pintype "power_in"))
      (node (ref "U2") (pin "F5") (pinfunction "VDD2_F5") (pintype "power_in"))
      (node (ref "U2") (pin "F8") (pinfunction "VDD2_F8") (pintype "power_in"))
      (node (ref "U2") (pin "H1") (pinfunction "VDD2_H1") (pintype "power_in"))
      (node (ref "U2") (pin "H12") (pinfunction "VDD2_H12") (pintype "power_in"))
      (node (ref "U2") (pin "H5") (pinfunction "VDD2_H5") (pintype "power_in"))
      (node (ref "U2") (pin "H8") (pinfunction "VDD2_H8") (pintype "power_in"))
      (node (ref "U2") (pin "K1") (pinfunction "VDD2_K1") (pintype "power_in"))
      (node (ref "U2") (pin "K10") (pinfunction "VDD2_K10") (pintype "power_in"))
      (node (ref "U2") (pin "K12") (pinfunction "VDD2_K12") (pintype "power_in"))
      (node (ref "U2") (pin "K3") (pinfunction "VDD2_K3") (pintype "power_in"))
      (node (ref "U2") (pin "N1") (pinfunction "VDD2_N1") (pintype "power_in"))
      (node (ref "U2") (pin "N10") (pinfunction "VDD2_N10") (pintype "power_in"))
      (node (ref "U2") (pin "N12") (pinfunction "VDD2_N12") (pintype "power_in"))
      (node (ref "U2") (pin "N3") (pinfunction "VDD2_N3") (pintype "power_in"))
      (node (ref "U2") (pin "R1") (pinfunction "VDD2_R1") (pintype "power_in"))
      (node (ref "U2") (pin "R12") (pinfunction "VDD2_R12") (pintype "power_in"))
      (node (ref "U2") (pin "R5") (pinfunction "VDD2_R5") (pintype "power_in"))
      (node (ref "U2") (pin "R8") (pinfunction "VDD2_R8") (pintype "power_in"))
      (node (ref "U2") (pin "U10") (pinfunction "VDDQ_U10") (pintype "power_in"))
      (node (ref "U2") (pin "U3") (pinfunction "VDDQ_U3") (pintype "power_in"))
      (node (ref "U2") (pin "U5") (pinfunction "VDD2_U5") (pintype "power_in"))
      (node (ref "U2") (pin "U8") (pinfunction "VDD2_U8") (pintype "power_in"))
      (node (ref "U2") (pin "W1") (pinfunction "VDDQ_W1") (pintype "power_in"))
      (node (ref "U2") (pin "W12") (pinfunction "VDDQ_W12") (pintype "power_in"))
      (node (ref "U2") (pin "W5") (pinfunction "VDDQ_W5") (pintype "power_in"))
      (node (ref "U2") (pin "W8") (pinfunction "VDDQ_W8") (pintype "power_in"))
    )
    (net (code "97") (name "VPP_DDR_1V8") (class "Default")
      (node (ref "C118") (pin "2") (pinfunction "2_2") (pintype "passive"))
      (node (ref "C119") (pin "2") (pinfunction "2_2") (pintype "passive"))
      (node (ref "C120") (pin "2") (pinfunction "2_2") (pintype "passive"))
      (node (ref "C121") (pin "2") (pinfunction "2_2") (pintype "passive"))
      (node (ref "C122") (pin "2") (pinfunction "2_2") (pintype "passive"))
      (node (ref "C123") (pin "2") (pinfunction "2_2") (pintype "passive"))
      (node (ref "C124") (pin "2") (pinfunction "2_2") (pintype "passive"))
      (node (ref "C125") (pin "2") (pinfunction "2_2") (pintype "passive"))
      (node (ref "C126") (pin "2") (pinfunction "2_2") (pintype "passive"))
      (node (ref "U2") (pin "F1") (pinfunction "VDD1_F1") (pintype "power_in"))
      (node (ref "U2") (pin "F12") (pinfunction "VDD1_F12") (pintype "power_in"))
      (node (ref "U2") (pin "G4") (pinfunction "VDD1_G4") (pintype "power_in"))
      (node (ref "U2") (pin "G9") (pinfunction "VDD1_G9") (pintype "power_in"))
      (node (ref "U2") (pin "T4") (pinfunction "VDD1_T4") (pintype "power_in"))
      (node (ref "U2") (pin "T9") (pinfunction "VDD1_T9") (pintype "power_in"))
      (node (ref "U2") (pin "U1") (pinfunction "VDD1_U1") (pintype "power_in"))
      (node (ref "U2") (pin "U12") (pinfunction "VDD1_U12") (pintype "power_in"))
    )
    (net (code "98") (name "unconnected-(U2B-DNU-PadA1)") (class "Default")
      (node (ref "U2") (pin "A1") (pinfunction "DNU_A1") (pintype "passive"))
    )
    (net (code "99") (name "unconnected-(U2B-DNU-PadA2)") (class "Default")
      (node (ref "U2") (pin "A2") (pinfunction "DNU_A2") (pintype "passive"))
    )
    (net (code "100") (name "unconnected-(U2B-DNU-PadA11)") (class "Default")
      (node (ref "U2") (pin "A11") (pinfunction "DNU_A11") (pintype "passive"))
    )
    (net (code "101") (name "unconnected-(U2B-DNU-PadA12)") (class "Default")
      (node (ref "U2") (pin "A12") (pinfunction "DNU_A12") (pintype "passive"))
    )
    (net (code "102") (name "unconnected-(U2B-DNU-PadAA1)") (class "Default")
      (node (ref "U2") (pin "AA1") (pinfunction "DNU_AA1") (pintype "passive"))
    )
    (net (code "103") (name "unconnected-(U2B-DNU-PadAA12)") (class "Default")
      (node (ref "U2") (pin "AA12") (pinfunction "DNU_AA12") (pintype "passive"))
    )
    (net (code "104") (name "unconnected-(U2B-DNU-PadAB1)") (class "Default")
      (node (ref "U2") (pin "AB1") (pinfunction "DNU_AB1") (pintype "passive"))
    )
    (net (code "105") (name "unconnected-(U2B-DNU-PadAB2)") (class "Default")
      (node (ref "U2") (pin "AB2") (pinfunction "DNU_AB2") (pintype "passive"))
    )
    (net (code "106") (name "unconnected-(U2B-DNU-PadAB11)") (class "Default")
      (node (ref "U2") (pin "AB11") (pinfunction "DNU_AB11") (pintype "passive"))
    )
    (net (code "107") (name "unconnected-(U2B-DNU-PadAB12)") (class "Default")
      (node (ref "U2") (pin "AB12") (pinfunction "DNU_AB12") (pintype "passive"))
    )
    (net (code "108") (name "unconnected-(U2B-DNU-PadB1)") (class "Default")
      (node (ref "U2") (pin "B1") (pinfunction "DNU_B1") (pintype "passive"))
    )
    (net (code "109") (name "unconnected-(U2B-DNU-PadB12)") (class "Default")
      (node (ref "U2") (pin "B12") (pinfunction "DNU_B12") (pintype "passive"))
    )
    (net (code "110") (name "unconnected-(U2C-NC-PadG11)") (class "Default")
      (node (ref "U2") (pin "G11") (pinfunction "NC_G11") (pintype "passive+no_connect"))
    )
    (net (code "111") (name "unconnected-(U2C-NC-PadK5)") (class "Default")
      (node (ref "U2") (pin "K5") (pinfunction "NC_K5") (pintype "passive+no_connect"))
    )
    (net (code "112") (name "unconnected-(U2C-NC-PadK8)") (class "Default")
      (node (ref "U2") (pin "K8") (pinfunction "NC_K8") (pintype "passive+no_connect"))
    )
    (net (code "113") (name "unconnected-(U2C-NC-PadN5)") (class "Default")
      (node (ref "U2") (pin "N5") (pinfunction "NC_N5") (pintype "passive+no_connect"))
    )
    (net (code "114") (name "unconnected-(U2C-NC-PadN8)") (class "Default")
      (node (ref "U2") (pin "N8") (pinfunction "NC_N8") (pintype "passive+no_connect"))
    )
  )
)
